# P2_tester.net
KiCad netlist of a schematic drawn in Altium Designer
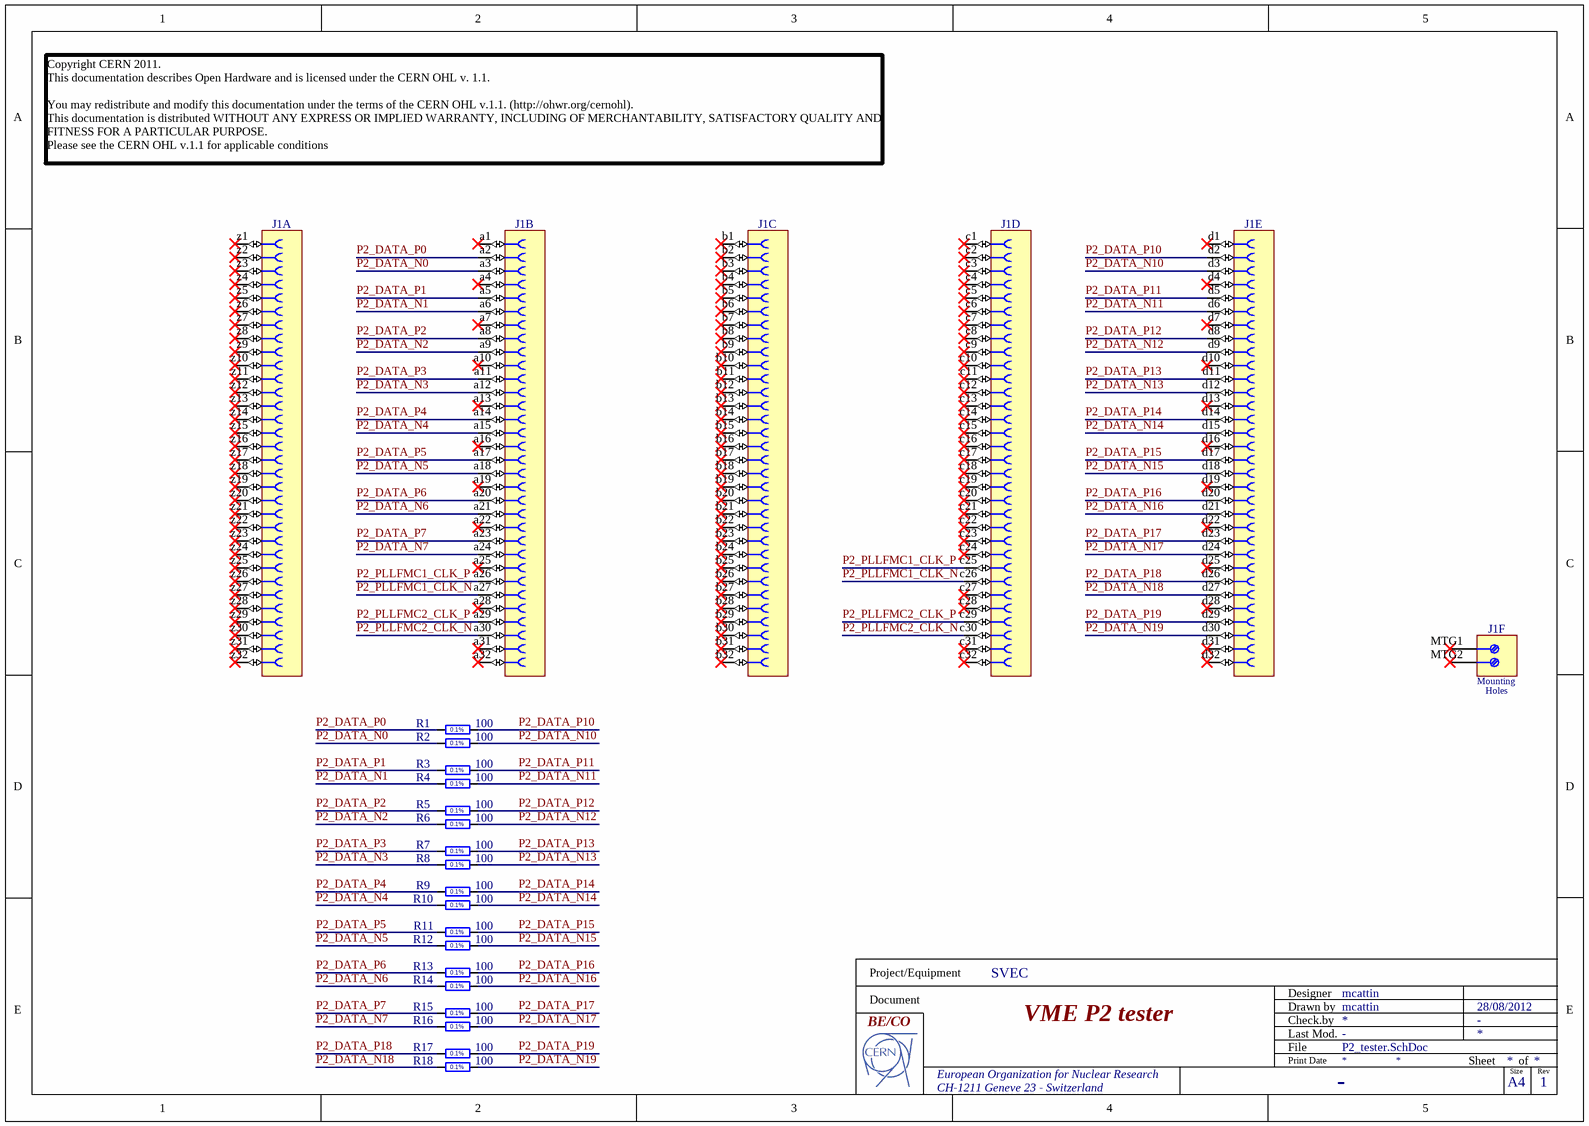
[diagram p0: P2_tester.SchDoc]

(export (version "E")
  (design (tool "Eeschema 10.0.6"))
  (components
    (comp (ref "J1")
      (value "HAR-BUS 64")
      (footprint "HARTING_02 04 160 1101")
      (description "Connector 160zabcd Female (5x32)")
      (fields
        (field (name "PART NUMBER") "HARTING_02 04 160 1101")
        (field (name "MANUFACTURER") "HARTING")
        (field (name "AUTHOR") "CERN DEM JLC")
      )
      (libsource (lib "Connectors") (part "Connector 160zabcd Female (5x32)"))
    )
    (comp (ref "R1")
      (value "100")
      (footprint "RESC1608X55N")
      (description "Resistor - 0.1%")
      (fields
        (field (name "PART NUMBER") "R0603_100R_0.1%_0.063W_10PPM")
        (field (name "POWER") "0.063W")
        (field (name "AUTHOR") "CERN DEM JLC")
      )
      (libsource (lib "Resistors") (part "Resistor - 0.1%"))
    )
    (comp (ref "R2")
      (value "100")
      (footprint "RESC1608X55N")
      (description "Resistor - 0.1%")
      (fields
        (field (name "PART NUMBER") "R0603_100R_0.1%_0.063W_10PPM")
        (field (name "POWER") "0.063W")
        (field (name "AUTHOR") "CERN DEM JLC")
      )
      (libsource (lib "Resistors") (part "Resistor - 0.1%"))
    )
    (comp (ref "R3")
      (value "100")
      (footprint "RESC1608X55N")
      (description "Resistor - 0.1%")
      (fields
        (field (name "PART NUMBER") "R0603_100R_0.1%_0.063W_10PPM")
        (field (name "POWER") "0.063W")
        (field (name "AUTHOR") "CERN DEM JLC")
      )
      (libsource (lib "Resistors") (part "Resistor - 0.1%"))
    )
    (comp (ref "R4")
      (value "100")
      (footprint "RESC1608X55N")
      (description "Resistor - 0.1%")
      (fields
        (field (name "PART NUMBER") "R0603_100R_0.1%_0.063W_10PPM")
        (field (name "POWER") "0.063W")
        (field (name "AUTHOR") "CERN DEM JLC")
      )
      (libsource (lib "Resistors") (part "Resistor - 0.1%"))
    )
    (comp (ref "R5")
      (value "100")
      (footprint "RESC1608X55N")
      (description "Resistor - 0.1%")
      (fields
        (field (name "PART NUMBER") "R0603_100R_0.1%_0.063W_10PPM")
        (field (name "POWER") "0.063W")
        (field (name "AUTHOR") "CERN DEM JLC")
      )
      (libsource (lib "Resistors") (part "Resistor - 0.1%"))
    )
    (comp (ref "R6")
      (value "100")
      (footprint "RESC1608X55N")
      (description "Resistor - 0.1%")
      (fields
        (field (name "PART NUMBER") "R0603_100R_0.1%_0.063W_10PPM")
        (field (name "POWER") "0.063W")
        (field (name "AUTHOR") "CERN DEM JLC")
      )
      (libsource (lib "Resistors") (part "Resistor - 0.1%"))
    )
    (comp (ref "R7")
      (value "100")
      (footprint "RESC1608X55N")
      (description "Resistor - 0.1%")
      (fields
        (field (name "PART NUMBER") "R0603_100R_0.1%_0.063W_10PPM")
        (field (name "POWER") "0.063W")
        (field (name "AUTHOR") "CERN DEM JLC")
      )
      (libsource (lib "Resistors") (part "Resistor - 0.1%"))
    )
    (comp (ref "R8")
      (value "100")
      (footprint "RESC1608X55N")
      (description "Resistor - 0.1%")
      (fields
        (field (name "PART NUMBER") "R0603_100R_0.1%_0.063W_10PPM")
        (field (name "POWER") "0.063W")
        (field (name "AUTHOR") "CERN DEM JLC")
      )
      (libsource (lib "Resistors") (part "Resistor - 0.1%"))
    )
    (comp (ref "R9")
      (value "100")
      (footprint "RESC1608X55N")
      (description "Resistor - 0.1%")
      (fields
        (field (name "PART NUMBER") "R0603_100R_0.1%_0.063W_10PPM")
        (field (name "POWER") "0.063W")
        (field (name "AUTHOR") "CERN DEM JLC")
      )
      (libsource (lib "Resistors") (part "Resistor - 0.1%"))
    )
    (comp (ref "R10")
      (value "100")
      (footprint "RESC1608X55N")
      (description "Resistor - 0.1%")
      (fields
        (field (name "PART NUMBER") "R0603_100R_0.1%_0.063W_10PPM")
        (field (name "POWER") "0.063W")
        (field (name "AUTHOR") "CERN DEM JLC")
      )
      (libsource (lib "Resistors") (part "Resistor - 0.1%"))
    )
    (comp (ref "R11")
      (value "100")
      (footprint "RESC1608X55N")
      (description "Resistor - 0.1%")
      (fields
        (field (name "PART NUMBER") "R0603_100R_0.1%_0.063W_10PPM")
        (field (name "POWER") "0.063W")
        (field (name "AUTHOR") "CERN DEM JLC")
      )
      (libsource (lib "Resistors") (part "Resistor - 0.1%"))
    )
    (comp (ref "R12")
      (value "100")
      (footprint "RESC1608X55N")
      (description "Resistor - 0.1%")
      (fields
        (field (name "PART NUMBER") "R0603_100R_0.1%_0.063W_10PPM")
        (field (name "POWER") "0.063W")
        (field (name "AUTHOR") "CERN DEM JLC")
      )
      (libsource (lib "Resistors") (part "Resistor - 0.1%"))
    )
    (comp (ref "R13")
      (value "100")
      (footprint "RESC1608X55N")
      (description "Resistor - 0.1%")
      (fields
        (field (name "PART NUMBER") "R0603_100R_0.1%_0.063W_10PPM")
        (field (name "POWER") "0.063W")
        (field (name "AUTHOR") "CERN DEM JLC")
      )
      (libsource (lib "Resistors") (part "Resistor - 0.1%"))
    )
    (comp (ref "R14")
      (value "100")
      (footprint "RESC1608X55N")
      (description "Resistor - 0.1%")
      (fields
        (field (name "PART NUMBER") "R0603_100R_0.1%_0.063W_10PPM")
        (field (name "POWER") "0.063W")
        (field (name "AUTHOR") "CERN DEM JLC")
      )
      (libsource (lib "Resistors") (part "Resistor - 0.1%"))
    )
    (comp (ref "R15")
      (value "100")
      (footprint "RESC1608X55N")
      (description "Resistor - 0.1%")
      (fields
        (field (name "PART NUMBER") "R0603_100R_0.1%_0.063W_10PPM")
        (field (name "POWER") "0.063W")
        (field (name "AUTHOR") "CERN DEM JLC")
      )
      (libsource (lib "Resistors") (part "Resistor - 0.1%"))
    )
    (comp (ref "R16")
      (value "100")
      (footprint "RESC1608X55N")
      (description "Resistor - 0.1%")
      (fields
        (field (name "PART NUMBER") "R0603_100R_0.1%_0.063W_10PPM")
        (field (name "POWER") "0.063W")
        (field (name "AUTHOR") "CERN DEM JLC")
      )
      (libsource (lib "Resistors") (part "Resistor - 0.1%"))
    )
    (comp (ref "R17")
      (value "100")
      (footprint "RESC1608X55N")
      (description "Resistor - 0.1%")
      (fields
        (field (name "PART NUMBER") "R0603_100R_0.1%_0.063W_10PPM")
        (field (name "POWER") "0.063W")
        (field (name "AUTHOR") "CERN DEM JLC")
      )
      (libsource (lib "Resistors") (part "Resistor - 0.1%"))
    )
    (comp (ref "R18")
      (value "100")
      (footprint "RESC1608X55N")
      (description "Resistor - 0.1%")
      (fields
        (field (name "PART NUMBER") "R0603_100R_0.1%_0.063W_10PPM")
        (field (name "POWER") "0.063W")
        (field (name "AUTHOR") "CERN DEM JLC")
      )
      (libsource (lib "Resistors") (part "Resistor - 0.1%"))
    )
  )
  (nets
    (net (code "1") (name "/P2_DATA_N0") (class "Default")
      (node (ref "J1") (pin "a3") (pinfunction "a3_a3") (pintype "bidirectional"))
      (node (ref "R2") (pin "1") (pinfunction "1_1") (pintype "passive"))
    )
    (net (code "2") (name "/P2_DATA_N1") (class "Default")
      (node (ref "J1") (pin "a6") (pinfunction "a6_a6") (pintype "bidirectional"))
      (node (ref "R4") (pin "1") (pinfunction "1_1") (pintype "passive"))
    )
    (net (code "3") (name "/P2_DATA_N2") (class "Default")
      (node (ref "J1") (pin "a9") (pinfunction "a9_a9") (pintype "bidirectional"))
      (node (ref "R6") (pin "1") (pinfunction "1_1") (pintype "passive"))
    )
    (net (code "4") (name "/P2_DATA_N3") (class "Default")
      (node (ref "J1") (pin "a12") (pinfunction "a12_a12") (pintype "bidirectional"))
      (node (ref "R8") (pin "1") (pinfunction "1_1") (pintype "passive"))
    )
    (net (code "5") (name "/P2_DATA_N4") (class "Default")
      (node (ref "J1") (pin "a15") (pinfunction "a15_a15") (pintype "bidirectional"))
      (node (ref "R10") (pin "1") (pinfunction "1_1") (pintype "passive"))
    )
    (net (code "6") (name "/P2_DATA_N5") (class "Default")
      (node (ref "J1") (pin "a18") (pinfunction "a18_a18") (pintype "bidirectional"))
      (node (ref "R12") (pin "1") (pinfunction "1_1") (pintype "passive"))
    )
    (net (code "7") (name "/P2_DATA_N6") (class "Default")
      (node (ref "J1") (pin "a21") (pinfunction "a21_a21") (pintype "bidirectional"))
      (node (ref "R14") (pin "1") (pinfunction "1_1") (pintype "passive"))
    )
    (net (code "8") (name "/P2_DATA_N7") (class "Default")
      (node (ref "J1") (pin "a24") (pinfunction "a24_a24") (pintype "bidirectional"))
      (node (ref "R16") (pin "1") (pinfunction "1_1") (pintype "passive"))
    )
    (net (code "9") (name "/P2_DATA_N10") (class "Default")
      (node (ref "J1") (pin "d3") (pinfunction "d3_d3") (pintype "bidirectional"))
      (node (ref "R2") (pin "2") (pinfunction "2_2") (pintype "passive"))
    )
    (net (code "10") (name "/P2_DATA_N11") (class "Default")
      (node (ref "J1") (pin "d6") (pinfunction "d6_d6") (pintype "bidirectional"))
      (node (ref "R4") (pin "2") (pinfunction "2_2") (pintype "passive"))
    )
    (net (code "11") (name "/P2_DATA_N12") (class "Default")
      (node (ref "J1") (pin "d9") (pinfunction "d9_d9") (pintype "bidirectional"))
      (node (ref "R6") (pin "2") (pinfunction "2_2") (pintype "passive"))
    )
    (net (code "12") (name "/P2_DATA_N13") (class "Default")
      (node (ref "J1") (pin "d12") (pinfunction "d12_d12") (pintype "bidirectional"))
      (node (ref "R8") (pin "2") (pinfunction "2_2") (pintype "passive"))
    )
    (net (code "13") (name "/P2_DATA_N14") (class "Default")
      (node (ref "J1") (pin "d15") (pinfunction "d15_d15") (pintype "bidirectional"))
      (node (ref "R10") (pin "2") (pinfunction "2_2") (pintype "passive"))
    )
    (net (code "14") (name "/P2_DATA_N15") (class "Default")
      (node (ref "J1") (pin "d18") (pinfunction "d18_d18") (pintype "bidirectional"))
      (node (ref "R12") (pin "2") (pinfunction "2_2") (pintype "passive"))
    )
    (net (code "15") (name "/P2_DATA_N16") (class "Default")
      (node (ref "J1") (pin "d21") (pinfunction "d21_d21") (pintype "bidirectional"))
      (node (ref "R14") (pin "2") (pinfunction "2_2") (pintype "passive"))
    )
    (net (code "16") (name "/P2_DATA_N17") (class "Default")
      (node (ref "J1") (pin "d24") (pinfunction "d24_d24") (pintype "bidirectional"))
      (node (ref "R16") (pin "2") (pinfunction "2_2") (pintype "passive"))
    )
    (net (code "17") (name "/P2_DATA_N18") (class "Default")
      (node (ref "J1") (pin "d27") (pinfunction "d27_d27") (pintype "bidirectional"))
      (node (ref "R18") (pin "1") (pinfunction "1_1") (pintype "passive"))
    )
    (net (code "18") (name "/P2_DATA_N19") (class "Default")
      (node (ref "J1") (pin "d30") (pinfunction "d30_d30") (pintype "bidirectional"))
      (node (ref "R18") (pin "2") (pinfunction "2_2") (pintype "passive"))
    )
    (net (code "19") (name "/P2_DATA_P0") (class "Default")
      (node (ref "J1") (pin "a2") (pinfunction "a2_a2") (pintype "bidirectional"))
      (node (ref "R1") (pin "1") (pinfunction "1_1") (pintype "passive"))
    )
    (net (code "20") (name "/P2_DATA_P1") (class "Default")
      (node (ref "J1") (pin "a5") (pinfunction "a5_a5") (pintype "bidirectional"))
      (node (ref "R3") (pin "1") (pinfunction "1_1") (pintype "passive"))
    )
    (net (code "21") (name "/P2_DATA_P2") (class "Default")
      (node (ref "J1") (pin "a8") (pinfunction "a8_a8") (pintype "bidirectional"))
      (node (ref "R5") (pin "1") (pinfunction "1_1") (pintype "passive"))
    )
    (net (code "22") (name "/P2_DATA_P3") (class "Default")
      (node (ref "J1") (pin "a11") (pinfunction "a11_a11") (pintype "bidirectional"))
      (node (ref "R7") (pin "1") (pinfunction "1_1") (pintype "passive"))
    )
    (net (code "23") (name "/P2_DATA_P4") (class "Default")
      (node (ref "J1") (pin "a14") (pinfunction "a14_a14") (pintype "bidirectional"))
      (node (ref "R9") (pin "1") (pinfunction "1_1") (pintype "passive"))
    )
    (net (code "24") (name "/P2_DATA_P5") (class "Default")
      (node (ref "J1") (pin "a17") (pinfunction "a17_a17") (pintype "bidirectional"))
      (node (ref "R11") (pin "1") (pinfunction "1_1") (pintype "passive"))
    )
    (net (code "25") (name "/P2_DATA_P6") (class "Default")
      (node (ref "J1") (pin "a20") (pinfunction "a20_a20") (pintype "bidirectional"))
      (node (ref "R13") (pin "1") (pinfunction "1_1") (pintype "passive"))
    )
    (net (code "26") (name "/P2_DATA_P7") (class "Default")
      (node (ref "J1") (pin "a23") (pinfunction "a23_a23") (pintype "bidirectional"))
      (node (ref "R15") (pin "1") (pinfunction "1_1") (pintype "passive"))
    )
    (net (code "27") (name "/P2_DATA_P10") (class "Default")
      (node (ref "J1") (pin "d2") (pinfunction "d2_d2") (pintype "bidirectional"))
      (node (ref "R1") (pin "2") (pinfunction "2_2") (pintype "passive"))
    )
    (net (code "28") (name "/P2_DATA_P11") (class "Default")
      (node (ref "J1") (pin "d5") (pinfunction "d5_d5") (pintype "bidirectional"))
      (node (ref "R3") (pin "2") (pinfunction "2_2") (pintype "passive"))
    )
    (net (code "29") (name "/P2_DATA_P12") (class "Default")
      (node (ref "J1") (pin "d8") (pinfunction "d8_d8") (pintype "bidirectional"))
      (node (ref "R5") (pin "2") (pinfunction "2_2") (pintype "passive"))
    )
    (net (code "30") (name "/P2_DATA_P13") (class "Default")
      (node (ref "J1") (pin "d11") (pinfunction "d11_d11") (pintype "bidirectional"))
      (node (ref "R7") (pin "2") (pinfunction "2_2") (pintype "passive"))
    )
    (net (code "31") (name "/P2_DATA_P14") (class "Default")
      (node (ref "J1") (pin "d14") (pinfunction "d14_d14") (pintype "bidirectional"))
      (node (ref "R9") (pin "2") (pinfunction "2_2") (pintype "passive"))
    )
    (net (code "32") (name "/P2_DATA_P15") (class "Default")
      (node (ref "J1") (pin "d17") (pinfunction "d17_d17") (pintype "bidirectional"))
      (node (ref "R11") (pin "2") (pinfunction "2_2") (pintype "passive"))
    )
    (net (code "33") (name "/P2_DATA_P16") (class "Default")
      (node (ref "J1") (pin "d20") (pinfunction "d20_d20") (pintype "bidirectional"))
      (node (ref "R13") (pin "2") (pinfunction "2_2") (pintype "passive"))
    )
    (net (code "34") (name "/P2_DATA_P17") (class "Default")
      (node (ref "J1") (pin "d23") (pinfunction "d23_d23") (pintype "bidirectional"))
      (node (ref "R15") (pin "2") (pinfunction "2_2") (pintype "passive"))
    )
    (net (code "35") (name "/P2_DATA_P18") (class "Default")
      (node (ref "J1") (pin "d26") (pinfunction "d26_d26") (pintype "bidirectional"))
      (node (ref "R17") (pin "1") (pinfunction "1_1") (pintype "passive"))
    )
    (net (code "36") (name "/P2_DATA_P19") (class "Default")
      (node (ref "J1") (pin "d29") (pinfunction "d29_d29") (pintype "bidirectional"))
      (node (ref "R17") (pin "2") (pinfunction "2_2") (pintype "passive"))
    )
    (net (code "37") (name "/P2_PLLFMC1_CLK_N") (class "Default")
      (node (ref "J1") (pin "a27") (pinfunction "a27_a27") (pintype "bidirectional"))
      (node (ref "J1") (pin "c26") (pinfunction "c26_c26") (pintype "bidirectional"))
    )
    (net (code "38") (name "/P2_PLLFMC1_CLK_P") (class "Default")
      (node (ref "J1") (pin "a26") (pinfunction "a26_a26") (pintype "bidirectional"))
      (node (ref "J1") (pin "c25") (pinfunction "c25_c25") (pintype "bidirectional"))
    )
    (net (code "39") (name "/P2_PLLFMC2_CLK_N") (class "Default")
      (node (ref "J1") (pin "a30") (pinfunction "a30_a30") (pintype "bidirectional"))
      (node (ref "J1") (pin "c30") (pinfunction "c30_c30") (pintype "bidirectional"))
    )
    (net (code "40") (name "/P2_PLLFMC2_CLK_P") (class "Default")
      (node (ref "J1") (pin "a29") (pinfunction "a29_a29") (pintype "bidirectional"))
      (node (ref "J1") (pin "c29") (pinfunction "c29_c29") (pintype "bidirectional"))
    )
    (net (code "41") (name "unconnected-(J1-PadMTG1)") (class "Default")
      (node (ref "J1") (pin "MTG1") (pinfunction "MTG1_MTG1") (pintype "passive+no_connect"))
    )
    (net (code "42") (name "unconnected-(J1-PadMTG2)") (class "Default")
      (node (ref "J1") (pin "MTG2") (pinfunction "MTG2_MTG2") (pintype "passive+no_connect"))
    )
    (net (code "43") (name "unconnected-(J1-Pada1)") (class "Default")
      (node (ref "J1") (pin "a1") (pinfunction "a1_a1") (pintype "bidirectional+no_connect"))
    )
    (net (code "44") (name "unconnected-(J1-Pada4)") (class "Default")
      (node (ref "J1") (pin "a4") (pinfunction "a4_a4") (pintype "bidirectional+no_connect"))
    )
    (net (code "45") (name "unconnected-(J1-Pada7)") (class "Default")
      (node (ref "J1") (pin "a7") (pinfunction "a7_a7") (pintype "bidirectional+no_connect"))
    )
    (net (code "46") (name "unconnected-(J1-Pada10)") (class "Default")
      (node (ref "J1") (pin "a10") (pinfunction "a10_a10") (pintype "bidirectional+no_connect"))
    )
    (net (code "47") (name "unconnected-(J1-Pada13)") (class "Default")
      (node (ref "J1") (pin "a13") (pinfunction "a13_a13") (pintype "bidirectional+no_connect"))
    )
    (net (code "48") (name "unconnected-(J1-Pada16)") (class "Default")
      (node (ref "J1") (pin "a16") (pinfunction "a16_a16") (pintype "bidirectional+no_connect"))
    )
    (net (code "49") (name "unconnected-(J1-Pada19)") (class "Default")
      (node (ref "J1") (pin "a19") (pinfunction "a19_a19") (pintype "bidirectional+no_connect"))
    )
    (net (code "50") (name "unconnected-(J1-Pada22)") (class "Default")
      (node (ref "J1") (pin "a22") (pinfunction "a22_a22") (pintype "bidirectional+no_connect"))
    )
    (net (code "51") (name "unconnected-(J1-Pada25)") (class "Default")
      (node (ref "J1") (pin "a25") (pinfunction "a25_a25") (pintype "bidirectional+no_connect"))
    )
    (net (code "52") (name "unconnected-(J1-Pada28)") (class "Default")
      (node (ref "J1") (pin "a28") (pinfunction "a28_a28") (pintype "bidirectional+no_connect"))
    )
    (net (code "53") (name "unconnected-(J1-Pada31)") (class "Default")
      (node (ref "J1") (pin "a31") (pinfunction "a31_a31") (pintype "bidirectional+no_connect"))
    )
    (net (code "54") (name "unconnected-(J1-Pada32)") (class "Default")
      (node (ref "J1") (pin "a32") (pinfunction "a32_a32") (pintype "bidirectional+no_connect"))
    )
    (net (code "55") (name "unconnected-(J1-Padb1)") (class "Default")
      (node (ref "J1") (pin "b1") (pinfunction "b1_b1") (pintype "bidirectional+no_connect"))
    )
    (net (code "56") (name "unconnected-(J1-Padb2)") (class "Default")
      (node (ref "J1") (pin "b2") (pinfunction "b2_b2") (pintype "bidirectional+no_connect"))
    )
    (net (code "57") (name "unconnected-(J1-Padb3)") (class "Default")
      (node (ref "J1") (pin "b3") (pinfunction "b3_b3") (pintype "bidirectional+no_connect"))
    )
    (net (code "58") (name "unconnected-(J1-Padb4)") (class "Default")
      (node (ref "J1") (pin "b4") (pinfunction "b4_b4") (pintype "bidirectional+no_connect"))
    )
    (net (code "59") (name "unconnected-(J1-Padb5)") (class "Default")
      (node (ref "J1") (pin "b5") (pinfunction "b5_b5") (pintype "bidirectional+no_connect"))
    )
    (net (code "60") (name "unconnected-(J1-Padb6)") (class "Default")
      (node (ref "J1") (pin "b6") (pinfunction "b6_b6") (pintype "bidirectional+no_connect"))
    )
    (net (code "61") (name "unconnected-(J1-Padb7)") (class "Default")
      (node (ref "J1") (pin "b7") (pinfunction "b7_b7") (pintype "bidirectional+no_connect"))
    )
    (net (code "62") (name "unconnected-(J1-Padb8)") (class "Default")
      (node (ref "J1") (pin "b8") (pinfunction "b8_b8") (pintype "bidirectional+no_connect"))
    )
    (net (code "63") (name "unconnected-(J1-Padb9)") (class "Default")
      (node (ref "J1") (pin "b9") (pinfunction "b9_b9") (pintype "bidirectional+no_connect"))
    )
    (net (code "64") (name "unconnected-(J1-Padb10)") (class "Default")
      (node (ref "J1") (pin "b10") (pinfunction "b10_b10") (pintype "bidirectional+no_connect"))
    )
    (net (code "65") (name "unconnected-(J1-Padb11)") (class "Default")
      (node (ref "J1") (pin "b11") (pinfunction "b11_b11") (pintype "bidirectional+no_connect"))
    )
    (net (code "66") (name "unconnected-(J1-Padb12)") (class "Default")
      (node (ref "J1") (pin "b12") (pinfunction "b12_b12") (pintype "bidirectional+no_connect"))
    )
    (net (code "67") (name "unconnected-(J1-Padb13)") (class "Default")
      (node (ref "J1") (pin "b13") (pinfunction "b13_b13") (pintype "bidirectional+no_connect"))
    )
    (net (code "68") (name "unconnected-(J1-Padb14)") (class "Default")
      (node (ref "J1") (pin "b14") (pinfunction "b14_b14") (pintype "bidirectional+no_connect"))
    )
    (net (code "69") (name "unconnected-(J1-Padb15)") (class "Default")
      (node (ref "J1") (pin "b15") (pinfunction "b15_b15") (pintype "bidirectional+no_connect"))
    )
    (net (code "70") (name "unconnected-(J1-Padb16)") (class "Default")
      (node (ref "J1") (pin "b16") (pinfunction "b16_b16") (pintype "bidirectional+no_connect"))
    )
    (net (code "71") (name "unconnected-(J1-Padb17)") (class "Default")
      (node (ref "J1") (pin "b17") (pinfunction "b17_b17") (pintype "bidirectional+no_connect"))
    )
    (net (code "72") (name "unconnected-(J1-Padb18)") (class "Default")
      (node (ref "J1") (pin "b18") (pinfunction "b18_b18") (pintype "bidirectional+no_connect"))
    )
    (net (code "73") (name "unconnected-(J1-Padb19)") (class "Default")
      (node (ref "J1") (pin "b19") (pinfunction "b19_b19") (pintype "bidirectional+no_connect"))
    )
    (net (code "74") (name "unconnected-(J1-Padb20)") (class "Default")
      (node (ref "J1") (pin "b20") (pinfunction "b20_b20") (pintype "bidirectional+no_connect"))
    )
    (net (code "75") (name "unconnected-(J1-Padb21)") (class "Default")
      (node (ref "J1") (pin "b21") (pinfunction "b21_b21") (pintype "bidirectional+no_connect"))
    )
    (net (code "76") (name "unconnected-(J1-Padb22)") (class "Default")
      (node (ref "J1") (pin "b22") (pinfunction "b22_b22") (pintype "bidirectional+no_connect"))
    )
    (net (code "77") (name "unconnected-(J1-Padb23)") (class "Default")
      (node (ref "J1") (pin "b23") (pinfunction "b23_b23") (pintype "bidirectional+no_connect"))
    )
    (net (code "78") (name "unconnected-(J1-Padb24)") (class "Default")
      (node (ref "J1") (pin "b24") (pinfunction "b24_b24") (pintype "bidirectional+no_connect"))
    )
    (net (code "79") (name "unconnected-(J1-Padb25)") (class "Default")
      (node (ref "J1") (pin "b25") (pinfunction "b25_b25") (pintype "bidirectional+no_connect"))
    )
    (net (code "80") (name "unconnected-(J1-Padb26)") (class "Default")
      (node (ref "J1") (pin "b26") (pinfunction "b26_b26") (pintype "bidirectional+no_connect"))
    )
    (net (code "81") (name "unconnected-(J1-Padb27)") (class "Default")
      (node (ref "J1") (pin "b27") (pinfunction "b27_b27") (pintype "bidirectional+no_connect"))
    )
    (net (code "82") (name "unconnected-(J1-Padb28)") (class "Default")
      (node (ref "J1") (pin "b28") (pinfunction "b28_b28") (pintype "bidirectional+no_connect"))
    )
    (net (code "83") (name "unconnected-(J1-Padb29)") (class "Default")
      (node (ref "J1") (pin "b29") (pinfunction "b29_b29") (pintype "bidirectional+no_connect"))
    )
    (net (code "84") (name "unconnected-(J1-Padb30)") (class "Default")
      (node (ref "J1") (pin "b30") (pinfunction "b30_b30") (pintype "bidirectional+no_connect"))
    )
    (net (code "85") (name "unconnected-(J1-Padb31)") (class "Default")
      (node (ref "J1") (pin "b31") (pinfunction "b31_b31") (pintype "bidirectional+no_connect"))
    )
    (net (code "86") (name "unconnected-(J1-Padb32)") (class "Default")
      (node (ref "J1") (pin "b32") (pinfunction "b32_b32") (pintype "bidirectional+no_connect"))
    )
    (net (code "87") (name "unconnected-(J1-Padc1)") (class "Default")
      (node (ref "J1") (pin "c1") (pinfunction "c1_c1") (pintype "bidirectional+no_connect"))
    )
    (net (code "88") (name "unconnected-(J1-Padc2)") (class "Default")
      (node (ref "J1") (pin "c2") (pinfunction "c2_c2") (pintype "bidirectional+no_connect"))
    )
    (net (code "89") (name "unconnected-(J1-Padc3)") (class "Default")
      (node (ref "J1") (pin "c3") (pinfunction "c3_c3") (pintype "bidirectional+no_connect"))
    )
    (net (code "90") (name "unconnected-(J1-Padc4)") (class "Default")
      (node (ref "J1") (pin "c4") (pinfunction "c4_c4") (pintype "bidirectional+no_connect"))
    )
    (net (code "91") (name "unconnected-(J1-Padc5)") (class "Default")
      (node (ref "J1") (pin "c5") (pinfunction "c5_c5") (pintype "bidirectional+no_connect"))
    )
    (net (code "92") (name "unconnected-(J1-Padc6)") (class "Default")
      (node (ref "J1") (pin "c6") (pinfunction "c6_c6") (pintype "bidirectional+no_connect"))
    )
    (net (code "93") (name "unconnected-(J1-Padc7)") (class "Default")
      (node (ref "J1") (pin "c7") (pinfunction "c7_c7") (pintype "bidirectional+no_connect"))
    )
    (net (code "94") (name "unconnected-(J1-Padc8)") (class "Default")
      (node (ref "J1") (pin "c8") (pinfunction "c8_c8") (pintype "bidirectional+no_connect"))
    )
    (net (code "95") (name "unconnected-(J1-Padc9)") (class "Default")
      (node (ref "J1") (pin "c9") (pinfunction "c9_c9") (pintype "bidirectional+no_connect"))
    )
    (net (code "96") (name "unconnected-(J1-Padc10)") (class "Default")
      (node (ref "J1") (pin "c10") (pinfunction "c10_c10") (pintype "bidirectional+no_connect"))
    )
    (net (code "97") (name "unconnected-(J1-Padc11)") (class "Default")
      (node (ref "J1") (pin "c11") (pinfunction "c11_c11") (pintype "bidirectional+no_connect"))
    )
    (net (code "98") (name "unconnected-(J1-Padc12)") (class "Default")
      (node (ref "J1") (pin "c12") (pinfunction "c12_c12") (pintype "bidirectional+no_connect"))
    )
    (net (code "99") (name "unconnected-(J1-Padc13)") (class "Default")
      (node (ref "J1") (pin "c13") (pinfunction "c13_c13") (pintype "bidirectional+no_connect"))
    )
    (net (code "100") (name "unconnected-(J1-Padc14)") (class "Default")
      (node (ref "J1") (pin "c14") (pinfunction "c14_c14") (pintype "bidirectional+no_connect"))
    )
    (net (code "101") (name "unconnected-(J1-Padc15)") (class "Default")
      (node (ref "J1") (pin "c15") (pinfunction "c15_c15") (pintype "bidirectional+no_connect"))
    )
    (net (code "102") (name "unconnected-(J1-Padc16)") (class "Default")
      (node (ref "J1") (pin "c16") (pinfunction "c16_c16") (pintype "bidirectional+no_connect"))
    )
    (net (code "103") (name "unconnected-(J1-Padc17)") (class "Default")
      (node (ref "J1") (pin "c17") (pinfunction "c17_c17") (pintype "bidirectional+no_connect"))
    )
    (net (code "104") (name "unconnected-(J1-Padc18)") (class "Default")
      (node (ref "J1") (pin "c18") (pinfunction "c18_c18") (pintype "bidirectional+no_connect"))
    )
    (net (code "105") (name "unconnected-(J1-Padc19)") (class "Default")
      (node (ref "J1") (pin "c19") (pinfunction "c19_c19") (pintype "bidirectional+no_connect"))
    )
    (net (code "106") (name "unconnected-(J1-Padc20)") (class "Default")
      (node (ref "J1") (pin "c20") (pinfunction "c20_c20") (pintype "bidirectional+no_connect"))
    )
    (net (code "107") (name "unconnected-(J1-Padc21)") (class "Default")
      (node (ref "J1") (pin "c21") (pinfunction "c21_c21") (pintype "bidirectional+no_connect"))
    )
    (net (code "108") (name "unconnected-(J1-Padc22)") (class "Default")
      (node (ref "J1") (pin "c22") (pinfunction "c22_c22") (pintype "bidirectional+no_connect"))
    )
    (net (code "109") (name "unconnected-(J1-Padc23)") (class "Default")
      (node (ref "J1") (pin "c23") (pinfunction "c23_c23") (pintype "bidirectional+no_connect"))
    )
    (net (code "110") (name "unconnected-(J1-Padc24)") (class "Default")
      (node (ref "J1") (pin "c24") (pinfunction "c24_c24") (pintype "bidirectional+no_connect"))
    )
    (net (code "111") (name "unconnected-(J1-Padc27)") (class "Default")
      (node (ref "J1") (pin "c27") (pinfunction "c27_c27") (pintype "bidirectional+no_connect"))
    )
    (net (code "112") (name "unconnected-(J1-Padc28)") (class "Default")
      (node (ref "J1") (pin "c28") (pinfunction "c28_c28") (pintype "bidirectional+no_connect"))
    )
    (net (code "113") (name "unconnected-(J1-Padc31)") (class "Default")
      (node (ref "J1") (pin "c31") (pinfunction "c31_c31") (pintype "bidirectional+no_connect"))
    )
    (net (code "114") (name "unconnected-(J1-Padc32)") (class "Default")
      (node (ref "J1") (pin "c32") (pinfunction "c32_c32") (pintype "bidirectional+no_connect"))
    )
    (net (code "115") (name "unconnected-(J1-Padd1)") (class "Default")
      (node (ref "J1") (pin "d1") (pinfunction "d1_d1") (pintype "bidirectional+no_connect"))
    )
    (net (code "116") (name "unconnected-(J1-Padd4)") (class "Default")
      (node (ref "J1") (pin "d4") (pinfunction "d4_d4") (pintype "bidirectional+no_connect"))
    )
    (net (code "117") (name "unconnected-(J1-Padd7)") (class "Default")
      (node (ref "J1") (pin "d7") (pinfunction "d7_d7") (pintype "bidirectional+no_connect"))
    )
    (net (code "118") (name "unconnected-(J1-Padd10)") (class "Default")
      (node (ref "J1") (pin "d10") (pinfunction "d10_d10") (pintype "bidirectional+no_connect"))
    )
    (net (code "119") (name "unconnected-(J1-Padd13)") (class "Default")
      (node (ref "J1") (pin "d13") (pinfunction "d13_d13") (pintype "bidirectional+no_connect"))
    )
    (net (code "120") (name "unconnected-(J1-Padd16)") (class "Default")
      (node (ref "J1") (pin "d16") (pinfunction "d16_d16") (pintype "bidirectional+no_connect"))
    )
    (net (code "121") (name "unconnected-(J1-Padd19)") (class "Default")
      (node (ref "J1") (pin "d19") (pinfunction "d19_d19") (pintype "bidirectional+no_connect"))
    )
    (net (code "122") (name "unconnected-(J1-Padd22)") (class "Default")
      (node (ref "J1") (pin "d22") (pinfunction "d22_d22") (pintype "bidirectional+no_connect"))
    )
    (net (code "123") (name "unconnected-(J1-Padd25)") (class "Default")
      (node (ref "J1") (pin "d25") (pinfunction "d25_d25") (pintype "bidirectional+no_connect"))
    )
    (net (code "124") (name "unconnected-(J1-Padd28)") (class "Default")
      (node (ref "J1") (pin "d28") (pinfunction "d28_d28") (pintype "bidirectional+no_connect"))
    )
    (net (code "125") (name "unconnected-(J1-Padd31)") (class "Default")
      (node (ref "J1") (pin "d31") (pinfunction "d31_d31") (pintype "bidirectional+no_connect"))
    )
    (net (code "126") (name "unconnected-(J1-Padd32)") (class "Default")
      (node (ref "J1") (pin "d32") (pinfunction "d32_d32") (pintype "bidirectional+no_connect"))
    )
    (net (code "127") (name "unconnected-(J1-Padz1)") (class "Default")
      (node (ref "J1") (pin "z1") (pinfunction "z1_z1") (pintype "bidirectional+no_connect"))
    )
    (net (code "128") (name "unconnected-(J1-Padz2)") (class "Default")
      (node (ref "J1") (pin "z2") (pinfunction "z2_z2") (pintype "bidirectional+no_connect"))
    )
    (net (code "129") (name "unconnected-(J1-Padz3)") (class "Default")
      (node (ref "J1") (pin "z3") (pinfunction "z3_z3") (pintype "bidirectional+no_connect"))
    )
    (net (code "130") (name "unconnected-(J1-Padz4)") (class "Default")
      (node (ref "J1") (pin "z4") (pinfunction "z4_z4") (pintype "bidirectional+no_connect"))
    )
    (net (code "131") (name "unconnected-(J1-Padz5)") (class "Default")
      (node (ref "J1") (pin "z5") (pinfunction "z5_z5") (pintype "bidirectional+no_connect"))
    )
    (net (code "132") (name "unconnected-(J1-Padz6)") (class "Default")
      (node (ref "J1") (pin "z6") (pinfunction "z6_z6") (pintype "bidirectional+no_connect"))
    )
    (net (code "133") (name "unconnected-(J1-Padz7)") (class "Default")
      (node (ref "J1") (pin "z7") (pinfunction "z7_z7") (pintype "bidirectional+no_connect"))
    )
    (net (code "134") (name "unconnected-(J1-Padz8)") (class "Default")
      (node (ref "J1") (pin "z8") (pinfunction "z8_z8") (pintype "bidirectional+no_connect"))
    )
    (net (code "135") (name "unconnected-(J1-Padz9)") (class "Default")
      (node (ref "J1") (pin "z9") (pinfunction "z9_z9") (pintype "bidirectional+no_connect"))
    )
    (net (code "136") (name "unconnected-(J1-Padz10)") (class "Default")
      (node (ref "J1") (pin "z10") (pinfunction "z10_z10") (pintype "bidirectional+no_connect"))
    )
    (net (code "137") (name "unconnected-(J1-Padz11)") (class "Default")
      (node (ref "J1") (pin "z11") (pinfunction "z11_z11") (pintype "bidirectional+no_connect"))
    )
    (net (code "138") (name "unconnected-(J1-Padz12)") (class "Default")
      (node (ref "J1") (pin "z12") (pinfunction "z12_z12") (pintype "bidirectional+no_connect"))
    )
    (net (code "139") (name "unconnected-(J1-Padz13)") (class "Default")
      (node (ref "J1") (pin "z13") (pinfunction "z13_z13") (pintype "bidirectional+no_connect"))
    )
    (net (code "140") (name "unconnected-(J1-Padz14)") (class "Default")
      (node (ref "J1") (pin "z14") (pinfunction "z14_z14") (pintype "bidirectional+no_connect"))
    )
    (net (code "141") (name "unconnected-(J1-Padz15)") (class "Default")
      (node (ref "J1") (pin "z15") (pinfunction "z15_z15") (pintype "bidirectional+no_connect"))
    )
    (net (code "142") (name "unconnected-(J1-Padz16)") (class "Default")
      (node (ref "J1") (pin "z16") (pinfunction "z16_z16") (pintype "bidirectional+no_connect"))
    )
    (net (code "143") (name "unconnected-(J1-Padz17)") (class "Default")
      (node (ref "J1") (pin "z17") (pinfunction "z17_z17") (pintype "bidirectional+no_connect"))
    )
    (net (code "144") (name "unconnected-(J1-Padz18)") (class "Default")
      (node (ref "J1") (pin "z18") (pinfunction "z18_z18") (pintype "bidirectional+no_connect"))
    )
    (net (code "145") (name "unconnected-(J1-Padz19)") (class "Default")
      (node (ref "J1") (pin "z19") (pinfunction "z19_z19") (pintype "bidirectional+no_connect"))
    )
    (net (code "146") (name "unconnected-(J1-Padz20)") (class "Default")
      (node (ref "J1") (pin "z20") (pinfunction "z20_z20") (pintype "bidirectional+no_connect"))
    )
    (net (code "147") (name "unconnected-(J1-Padz21)") (class "Default")
      (node (ref "J1") (pin "z21") (pinfunction "z21_z21") (pintype "bidirectional+no_connect"))
    )
    (net (code "148") (name "unconnected-(J1-Padz22)") (class "Default")
      (node (ref "J1") (pin "z22") (pinfunction "z22_z22") (pintype "bidirectional+no_connect"))
    )
    (net (code "149") (name "unconnected-(J1-Padz23)") (class "Default")
      (node (ref "J1") (pin "z23") (pinfunction "z23_z23") (pintype "bidirectional+no_connect"))
    )
    (net (code "150") (name "unconnected-(J1-Padz24)") (class "Default")
      (node (ref "J1") (pin "z24") (pinfunction "z24_z24") (pintype "bidirectional+no_connect"))
    )
    (net (code "151") (name "unconnected-(J1-Padz25)") (class "Default")
      (node (ref "J1") (pin "z25") (pinfunction "z25_z25") (pintype "bidirectional+no_connect"))
    )
    (net (code "152") (name "unconnected-(J1-Padz26)") (class "Default")
      (node (ref "J1") (pin "z26") (pinfunction "z26_z26") (pintype "bidirectional+no_connect"))
    )
    (net (code "153") (name "unconnected-(J1-Padz27)") (class "Default")
      (node (ref "J1") (pin "z27") (pinfunction "z27_z27") (pintype "bidirectional+no_connect"))
    )
    (net (code "154") (name "unconnected-(J1-Padz28)") (class "Default")
      (node (ref "J1") (pin "z28") (pinfunction "z28_z28") (pintype "bidirectional+no_connect"))
    )
    (net (code "155") (name "unconnected-(J1-Padz29)") (class "Default")
      (node (ref "J1") (pin "z29") (pinfunction "z29_z29") (pintype "bidirectional+no_connect"))
    )
    (net (code "156") (name "unconnected-(J1-Padz30)") (class "Default")
      (node (ref "J1") (pin "z30") (pinfunction "z30_z30") (pintype "bidirectional+no_connect"))
    )
    (net (code "157") (name "unconnected-(J1-Padz31)") (class "Default")
      (node (ref "J1") (pin "z31") (pinfunction "z31_z31") (pintype "bidirectional+no_connect"))
    )
    (net (code "158") (name "unconnected-(J1-Padz32)") (class "Default")
      (node (ref "J1") (pin "z32") (pinfunction "z32_z32") (pintype "bidirectional+no_connect"))
    )
  )
)
